# 05-VIDEO_IN_ADC_1.net
KiCad netlist of a schematic drawn in Altium Designer
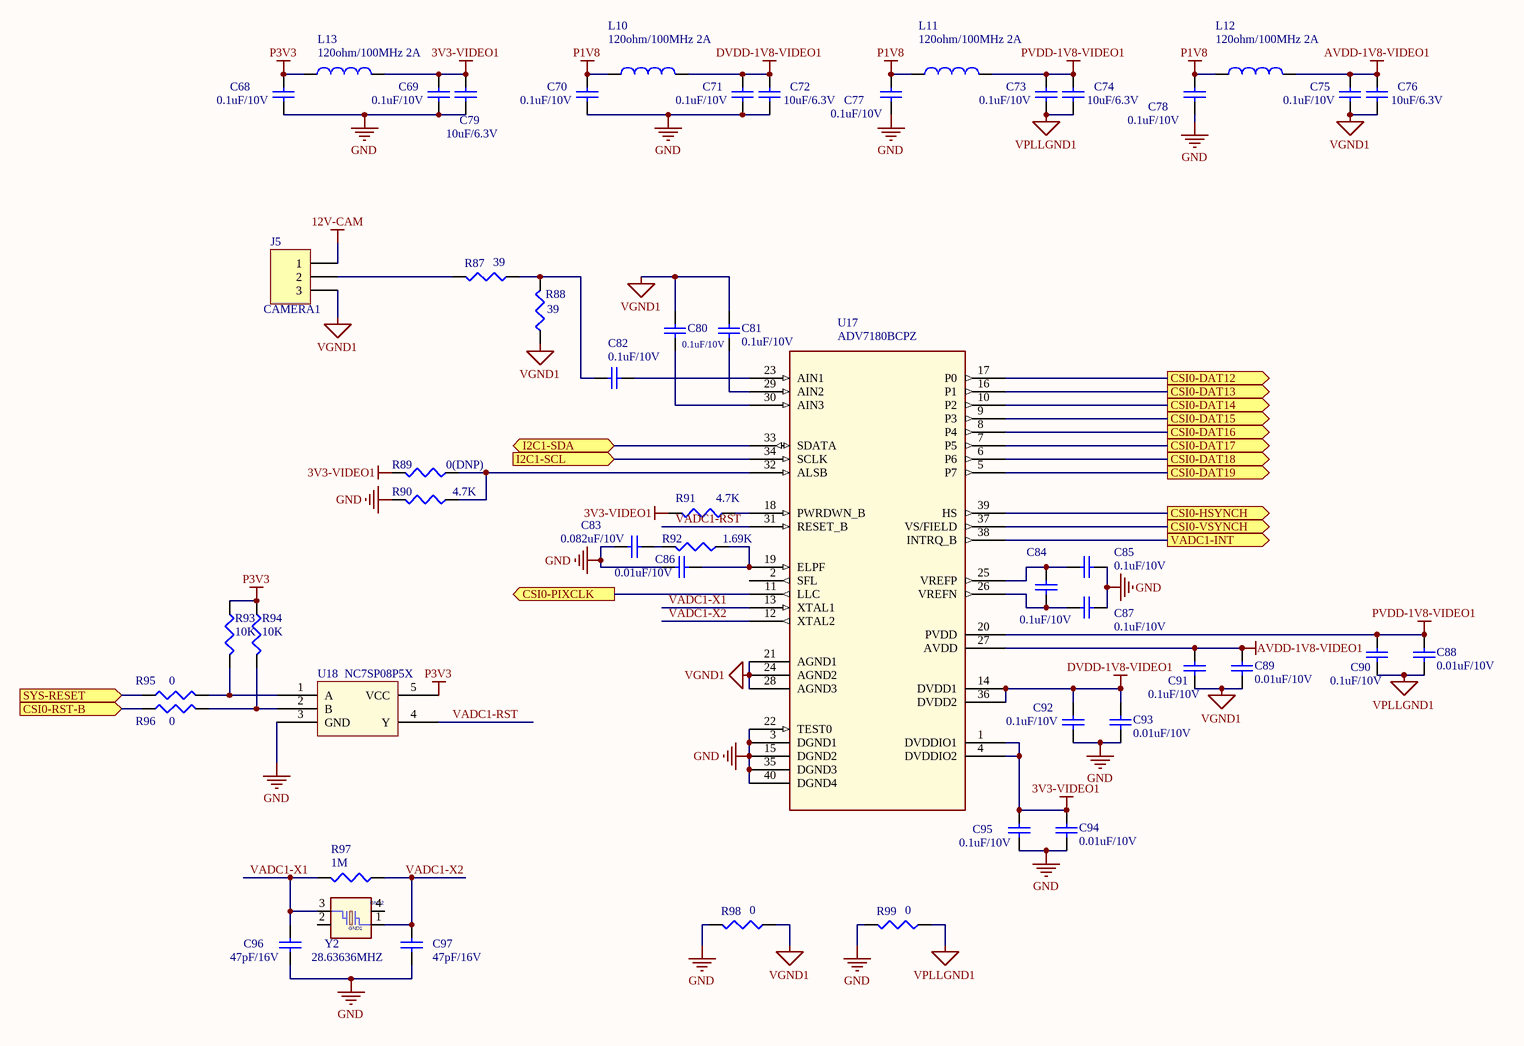
[diagram p0: 05-VIDEO_IN_ADC_1.SchDoc]

(export (version "E")
  (design (tool "Eeschema 10.0.6"))
  (components
    (comp (ref "C68")
      (value "0.1uF/10V")
      (footprint "0402")
      (description "Capacitor")
      (fields (field (name "PUBLISHER") "Altium Limited"))
      (libsource (lib "Miscellaneous Devices") (part "Cap"))
    )
    (comp (ref "C69")
      (value "0.1uF/10V")
      (footprint "0402")
      (description "Capacitor")
      (fields (field (name "PUBLISHER") "Altium Limited"))
      (libsource (lib "Miscellaneous Devices") (part "Cap"))
    )
    (comp (ref "C70")
      (value "0.1uF/10V")
      (footprint "0402")
      (description "Capacitor")
      (fields (field (name "PUBLISHER") "Altium Limited"))
      (libsource (lib "Miscellaneous Devices") (part "Cap"))
    )
    (comp (ref "C71")
      (value "0.1uF/10V")
      (footprint "0402")
      (description "Capacitor")
      (fields (field (name "PUBLISHER") "Altium Limited"))
      (libsource (lib "Miscellaneous Devices") (part "Cap"))
    )
    (comp (ref "C72")
      (value "10uF/6.3V")
      (footprint "0805")
      (description "Capacitor")
      (fields (field (name "PUBLISHER") "Altium Limited"))
      (libsource (lib "Miscellaneous Devices") (part "Cap"))
    )
    (comp (ref "C73")
      (value "0.1uF/10V")
      (footprint "0402")
      (description "Capacitor")
      (fields (field (name "PUBLISHER") "Altium Limited"))
      (libsource (lib "Miscellaneous Devices") (part "Cap"))
    )
    (comp (ref "C74")
      (value "10uF/6.3V")
      (footprint "0805")
      (description "Capacitor")
      (fields (field (name "PUBLISHER") "Altium Limited"))
      (libsource (lib "Miscellaneous Devices") (part "Cap"))
    )
    (comp (ref "C75")
      (value "0.1uF/10V")
      (footprint "0402")
      (description "Capacitor")
      (fields (field (name "PUBLISHER") "Altium Limited"))
      (libsource (lib "Miscellaneous Devices") (part "Cap"))
    )
    (comp (ref "C76")
      (value "10uF/6.3V")
      (footprint "0805")
      (description "Capacitor")
      (fields (field (name "PUBLISHER") "Altium Limited"))
      (libsource (lib "Miscellaneous Devices") (part "Cap"))
    )
    (comp (ref "C77")
      (value "0.1uF/10V")
      (footprint "0402")
      (description "Capacitor")
      (fields (field (name "PUBLISHER") "Altium Limited"))
      (libsource (lib "Miscellaneous Devices") (part "Cap"))
    )
    (comp (ref "C78")
      (value "0.1uF/10V")
      (footprint "0402")
      (description "Capacitor")
      (fields (field (name "PUBLISHER") "Altium Limited"))
      (libsource (lib "Miscellaneous Devices") (part "Cap"))
    )
    (comp (ref "C79")
      (value "10uF/6.3V")
      (footprint "0805")
      (description "Capacitor")
      (fields (field (name "PUBLISHER") "Altium Limited"))
      (libsource (lib "Miscellaneous Devices") (part "Cap"))
    )
    (comp (ref "C80")
      (value "0.1uF/10V")
      (footprint "0402")
      (description "Capacitor")
      (fields (field (name "PUBLISHER") "Altium Limited"))
      (libsource (lib "Miscellaneous Devices") (part "Cap"))
    )
    (comp (ref "C81")
      (value "0.1uF/10V")
      (footprint "0402")
      (description "Capacitor")
      (fields (field (name "PUBLISHER") "Altium Limited"))
      (libsource (lib "Miscellaneous Devices") (part "Cap"))
    )
    (comp (ref "C82")
      (value "0.1uF/10V")
      (footprint "0402")
      (description "Capacitor")
      (fields (field (name "PUBLISHER") "Altium Limited"))
      (libsource (lib "Miscellaneous Devices") (part "Cap"))
    )
    (comp (ref "C83")
      (value "0.082uF/10V")
      (footprint "0402")
      (description "Capacitor")
      (fields (field (name "PUBLISHER") "Altium Limited"))
      (libsource (lib "Miscellaneous Devices") (part "Cap"))
    )
    (comp (ref "C84")
      (value "0.1uF/10V")
      (footprint "0402")
      (description "Capacitor")
      (fields (field (name "PUBLISHER") "Altium Limited"))
      (libsource (lib "Miscellaneous Devices") (part "Cap"))
    )
    (comp (ref "C85")
      (value "0.1uF/10V")
      (footprint "0402")
      (description "Capacitor")
      (fields (field (name "PUBLISHER") "Altium Limited"))
      (libsource (lib "Miscellaneous Devices") (part "Cap"))
    )
    (comp (ref "C86")
      (value "0.01uF/10V")
      (footprint "0402")
      (description "Capacitor")
      (fields (field (name "PUBLISHER") "Altium Limited"))
      (libsource (lib "Miscellaneous Devices") (part "Cap"))
    )
    (comp (ref "C87")
      (value "0.1uF/10V")
      (footprint "0402")
      (description "Capacitor")
      (fields (field (name "PUBLISHER") "Altium Limited"))
      (libsource (lib "Miscellaneous Devices") (part "Cap"))
    )
    (comp (ref "C88")
      (value "0.01uF/10V")
      (footprint "0402")
      (description "Capacitor")
      (fields (field (name "PUBLISHER") "Altium Limited"))
      (libsource (lib "Miscellaneous Devices") (part "Cap"))
    )
    (comp (ref "C89")
      (value "0.01uF/10V")
      (footprint "0402")
      (description "Capacitor")
      (fields (field (name "PUBLISHER") "Altium Limited"))
      (libsource (lib "Miscellaneous Devices") (part "Cap"))
    )
    (comp (ref "C90")
      (value "0.1uF/10V")
      (footprint "0402")
      (description "Capacitor")
      (fields (field (name "PUBLISHER") "Altium Limited"))
      (libsource (lib "Miscellaneous Devices") (part "Cap"))
    )
    (comp (ref "C91")
      (value "0.1uF/10V")
      (footprint "0402")
      (description "Capacitor")
      (fields (field (name "PUBLISHER") "Altium Limited"))
      (libsource (lib "Miscellaneous Devices") (part "Cap"))
    )
    (comp (ref "C92")
      (value "0.1uF/10V")
      (footprint "0402")
      (description "Capacitor")
      (fields (field (name "PUBLISHER") "Altium Limited"))
      (libsource (lib "Miscellaneous Devices") (part "Cap"))
    )
    (comp (ref "C93")
      (value "0.01uF/10V")
      (footprint "0402")
      (description "Capacitor")
      (fields (field (name "PUBLISHER") "Altium Limited"))
      (libsource (lib "Miscellaneous Devices") (part "Cap"))
    )
    (comp (ref "C94")
      (value "0.01uF/10V")
      (footprint "0402")
      (description "Capacitor")
      (fields (field (name "PUBLISHER") "Altium Limited"))
      (libsource (lib "Miscellaneous Devices") (part "Cap"))
    )
    (comp (ref "C95")
      (value "0.1uF/10V")
      (footprint "0402")
      (description "Capacitor")
      (fields (field (name "PUBLISHER") "Altium Limited"))
      (libsource (lib "Miscellaneous Devices") (part "Cap"))
    )
    (comp (ref "C96")
      (value "47pF/16V")
      (footprint "0402")
      (description "Capacitor")
      (fields (field (name "PUBLISHER") "Altium Limited"))
      (libsource (lib "Miscellaneous Devices") (part "Cap"))
    )
    (comp (ref "C97")
      (value "47pF/16V")
      (footprint "0402")
      (description "Capacitor")
      (fields (field (name "PUBLISHER") "Altium Limited"))
      (libsource (lib "Miscellaneous Devices") (part "Cap"))
    )
    (comp (ref "J5")
      (value "CAMERA1")
      (footprint "CONN-3P")
      (description "Header, 3-Pin")
      (fields (field (name "PUBLISHER") "Altium Limited"))
      (libsource (lib "Miscellaneous Connectors") (part "Header 3"))
    )
    (comp (ref "L10")
      (value "120ohm/100MHz 2A")
      (footprint "0603")
      (description "Inductor")
      (fields (field (name "PUBLISHER") "Altium Limited"))
      (libsource (lib "Miscellaneous Devices") (part "Inductor"))
    )
    (comp (ref "L11")
      (value "120ohm/100MHz 2A")
      (footprint "0603")
      (description "Inductor")
      (fields (field (name "PUBLISHER") "Altium Limited"))
      (libsource (lib "Miscellaneous Devices") (part "Inductor"))
    )
    (comp (ref "L12")
      (value "120ohm/100MHz 2A")
      (footprint "0603")
      (description "Inductor")
      (fields (field (name "PUBLISHER") "Altium Limited"))
      (libsource (lib "Miscellaneous Devices") (part "Inductor"))
    )
    (comp (ref "L13")
      (value "120ohm/100MHz 2A")
      (footprint "0603")
      (description "Inductor")
      (fields (field (name "PUBLISHER") "Altium Limited"))
      (libsource (lib "Miscellaneous Devices") (part "Inductor"))
    )
    (comp (ref "R87") (value "39") (footprint "0402") (libsource (lib "*") (part "CR16-1003FM")))
    (comp (ref "R88") (value "39") (footprint "0402") (libsource (lib "*") (part "CR16-1003FM")))
    (comp (ref "R89") (value "0(DNP)") (footprint "0402") (libsource (lib "*") (part "CR16-1003FM")))
    (comp (ref "R90") (value "4.7K") (footprint "0402") (libsource (lib "*") (part "CR16-1003FM")))
    (comp (ref "R91") (value "4.7K") (footprint "0402") (libsource (lib "*") (part "CR16-1003FM")))
    (comp (ref "R92") (value "1.69K") (footprint "0402") (libsource (lib "*") (part "CR16-1003FM")))
    (comp (ref "R93") (value "10K") (footprint "0402") (libsource (lib "*") (part "CR16-1003FM")))
    (comp (ref "R94") (value "10K") (footprint "0402") (libsource (lib "*") (part "CR16-1003FM")))
    (comp (ref "R95") (value "0") (footprint "0402") (libsource (lib "*") (part "CR16-1003FM")))
    (comp (ref "R96") (value "0") (footprint "0402") (libsource (lib "*") (part "CR16-1003FM")))
    (comp (ref "R97") (value "1M") (footprint "0402") (libsource (lib "*") (part "CR16-1003FM")))
    (comp (ref "R98") (value "0") (footprint "0402") (libsource (lib "*") (part "CR16-1003FM")))
    (comp (ref "R99") (value "0") (footprint "0402") (libsource (lib "*") (part "CR16-1003FM")))
    (comp (ref "U17")
      (value "ADV7180BCPZ")
      (footprint "LFCSP40")
      (libsource (lib "Schlib") (part "ADV7180BCPZ"))
    )
    (comp (ref "U18") (value "NC7SP08P5X") (footprint "SC70") (libsource (lib "Schlib") (part "NC7SP08P5X")))
    (comp (ref "Y2")
      (value "28.63636MHZ")
      (footprint "XTAL4_SX_3225")
      (description "XTAL 28.63636MHZ 10PF RSN -- SMT")
      (libsource (lib "*") (part "CRYSTAL_JXS63"))
    )
  )
  (nets
    (net (code "1") (name "/CSI0-DAT12") (class "Default")
      (node (ref "U17") (pin "17") (pinfunction "P0_17") (pintype "output"))
    )
    (net (code "2") (name "/CSI0-DAT13") (class "Default")
      (node (ref "U17") (pin "16") (pinfunction "P1_16") (pintype "output"))
    )
    (net (code "3") (name "/CSI0-DAT14") (class "Default")
      (node (ref "U17") (pin "10") (pinfunction "P2_10") (pintype "output"))
    )
    (net (code "4") (name "/CSI0-DAT15") (class "Default")
      (node (ref "U17") (pin "9") (pinfunction "P3_9") (pintype "output"))
    )
    (net (code "5") (name "/CSI0-DAT16") (class "Default")
      (node (ref "U17") (pin "8") (pinfunction "P4_8") (pintype "output"))
    )
    (net (code "6") (name "/CSI0-DAT17") (class "Default")
      (node (ref "U17") (pin "7") (pinfunction "P5_7") (pintype "output"))
    )
    (net (code "7") (name "/CSI0-DAT18") (class "Default")
      (node (ref "U17") (pin "6") (pinfunction "P6_6") (pintype "output"))
    )
    (net (code "8") (name "/CSI0-DAT19") (class "Default")
      (node (ref "U17") (pin "5") (pinfunction "P7_5") (pintype "output"))
    )
    (net (code "9") (name "/CSI0-HSYNCH") (class "Default")
      (node (ref "U17") (pin "39") (pinfunction "HS_39") (pintype "output"))
    )
    (net (code "10") (name "/CSI0-PIXCLK") (class "Default")
      (node (ref "U17") (pin "11") (pinfunction "LLC_11") (pintype "output"))
    )
    (net (code "11") (name "/CSI0-RST-B") (class "Default")
      (node (ref "R96") (pin "1") (pinfunction "1_1") (pintype "passive"))
    )
    (net (code "12") (name "/CSI0-VSYNCH") (class "Default")
      (node (ref "U17") (pin "37") (pinfunction "VS/FIELD_37") (pintype "output"))
    )
    (net (code "13") (name "/I2C1-SCL") (class "Default")
      (node (ref "U17") (pin "34") (pinfunction "SCLK_34") (pintype "input"))
    )
    (net (code "14") (name "/I2C1-SDA") (class "Default")
      (node (ref "U17") (pin "33") (pinfunction "SDATA_33") (pintype "bidirectional"))
    )
    (net (code "15") (name "/SYS-RESET") (class "Default")
      (node (ref "R95") (pin "1") (pinfunction "1_1") (pintype "passive"))
    )
    (net (code "16") (name "/VADC1-INT") (class "Default")
      (node (ref "U17") (pin "38") (pinfunction "INTRQ_B_38") (pintype "output"))
    )
    (net (code "17") (name "/VADC1-RST") (class "Default")
      (node (ref "U17") (pin "31") (pinfunction "RESET_B_31") (pintype "input"))
      (node (ref "U18") (pin "4") (pinfunction "Y_4") (pintype "passive"))
    )
    (net (code "18") (name "/VADC1-X1") (class "Default")
      (node (ref "C96") (pin "2") (pinfunction "2_2") (pintype "passive"))
      (node (ref "R97") (pin "2") (pinfunction "2_2") (pintype "passive"))
      (node (ref "U17") (pin "13") (pinfunction "XTAL1_13") (pintype "input"))
      (node (ref "Y2") (pin "3") (pinfunction "3_3") (pintype "passive"))
    )
    (net (code "19") (name "/VADC1-X2") (class "Default")
      (node (ref "C97") (pin "2") (pinfunction "2_2") (pintype "passive"))
      (node (ref "R97") (pin "1") (pinfunction "1_1") (pintype "passive"))
      (node (ref "U17") (pin "12") (pinfunction "XTAL2_12") (pintype "output"))
      (node (ref "Y2") (pin "1") (pinfunction "1_1") (pintype "passive"))
    )
    (net (code "20") (name "3V3-VIDEO1") (class "Default")
      (node (ref "C69") (pin "1") (pinfunction "1_1") (pintype "passive"))
      (node (ref "C79") (pin "1") (pinfunction "1_1") (pintype "passive"))
      (node (ref "C94") (pin "2") (pinfunction "2_2") (pintype "passive"))
      (node (ref "C95") (pin "2") (pinfunction "2_2") (pintype "passive"))
      (node (ref "L13") (pin "2") (pinfunction "2_2") (pintype "passive"))
      (node (ref "R89") (pin "2") (pinfunction "2_2") (pintype "passive"))
      (node (ref "R91") (pin "2") (pinfunction "2_2") (pintype "passive"))
      (node (ref "U17") (pin "1") (pinfunction "DVDDIO1_1") (pintype "power_in"))
      (node (ref "U17") (pin "4") (pinfunction "DVDDIO2_4") (pintype "power_in"))
    )
    (net (code "21") (name "12V-CAM") (class "Default")
      (node (ref "J5") (pin "1") (pinfunction "1_1") (pintype "passive"))
    )
    (net (code "22") (name "AVDD-1V8-VIDEO1") (class "Default")
      (node (ref "C75") (pin "1") (pinfunction "1_1") (pintype "passive"))
      (node (ref "C76") (pin "1") (pinfunction "1_1") (pintype "passive"))
      (node (ref "C89") (pin "2") (pinfunction "2_2") (pintype "passive"))
      (node (ref "C91") (pin "2") (pinfunction "2_2") (pintype "passive"))
      (node (ref "L12") (pin "2") (pinfunction "2_2") (pintype "passive"))
      (node (ref "U17") (pin "27") (pinfunction "AVDD_27") (pintype "power_in"))
    )
    (net (code "23") (name "DVDD-1V8-VIDEO1") (class "Default")
      (node (ref "C71") (pin "1") (pinfunction "1_1") (pintype "passive"))
      (node (ref "C72") (pin "1") (pinfunction "1_1") (pintype "passive"))
      (node (ref "C92") (pin "2") (pinfunction "2_2") (pintype "passive"))
      (node (ref "C93") (pin "2") (pinfunction "2_2") (pintype "passive"))
      (node (ref "L10") (pin "2") (pinfunction "2_2") (pintype "passive"))
      (node (ref "U17") (pin "14") (pinfunction "DVDD1_14") (pintype "power_in"))
      (node (ref "U17") (pin "36") (pinfunction "DVDD2_36") (pintype "power_in"))
    )
    (net (code "24") (name "GND") (class "Default")
      (node (ref "C68") (pin "2") (pinfunction "2_2") (pintype "passive"))
      (node (ref "C69") (pin "2") (pinfunction "2_2") (pintype "passive"))
      (node (ref "C70") (pin "2") (pinfunction "2_2") (pintype "passive"))
      (node (ref "C71") (pin "2") (pinfunction "2_2") (pintype "passive"))
      (node (ref "C72") (pin "2") (pinfunction "2_2") (pintype "passive"))
      (node (ref "C77") (pin "2") (pinfunction "2_2") (pintype "passive"))
      (node (ref "C78") (pin "2") (pinfunction "2_2") (pintype "passive"))
      (node (ref "C79") (pin "2") (pinfunction "2_2") (pintype "passive"))
      (node (ref "C83") (pin "1") (pinfunction "1_1") (pintype "passive"))
      (node (ref "C85") (pin "1") (pinfunction "1_1") (pintype "passive"))
      (node (ref "C86") (pin "1") (pinfunction "1_1") (pintype "passive"))
      (node (ref "C87") (pin "2") (pinfunction "2_2") (pintype "passive"))
      (node (ref "C92") (pin "1") (pinfunction "1_1") (pintype "passive"))
      (node (ref "C93") (pin "1") (pinfunction "1_1") (pintype "passive"))
      (node (ref "C94") (pin "1") (pinfunction "1_1") (pintype "passive"))
      (node (ref "C95") (pin "1") (pinfunction "1_1") (pintype "passive"))
      (node (ref "C96") (pin "1") (pinfunction "1_1") (pintype "passive"))
      (node (ref "C97") (pin "1") (pinfunction "1_1") (pintype "passive"))
      (node (ref "R90") (pin "2") (pinfunction "2_2") (pintype "passive"))
      (node (ref "R98") (pin "2") (pinfunction "2_2") (pintype "passive"))
      (node (ref "R99") (pin "2") (pinfunction "2_2") (pintype "passive"))
      (node (ref "U17") (pin "15") (pinfunction "DGND2_15") (pintype "power_in"))
      (node (ref "U17") (pin "22") (pinfunction "TEST0_22") (pintype "input"))
      (node (ref "U17") (pin "3") (pinfunction "DGND1_3") (pintype "power_in"))
      (node (ref "U17") (pin "35") (pinfunction "DGND3_35") (pintype "power_in"))
      (node (ref "U17") (pin "40") (pinfunction "DGND4_40") (pintype "power_in"))
      (node (ref "U18") (pin "3") (pinfunction "GND_3") (pintype "passive"))
    )
    (net (code "25") (name "Net-(C82-Pad1)") (class "Default")
      (node (ref "C82") (pin "1") (pinfunction "1_1") (pintype "passive"))
      (node (ref "R87") (pin "1") (pinfunction "1_1") (pintype "passive"))
      (node (ref "R88") (pin "2") (pinfunction "2_2") (pintype "passive"))
    )
    (net (code "26") (name "Net-(C83-Pad2)") (class "Default")
      (node (ref "C83") (pin "2") (pinfunction "2_2") (pintype "passive"))
      (node (ref "R92") (pin "2") (pinfunction "2_2") (pintype "passive"))
    )
    (net (code "27") (name "Net-(J5-Pad2)") (class "Default")
      (node (ref "J5") (pin "2") (pinfunction "2_2") (pintype "passive"))
      (node (ref "R87") (pin "2") (pinfunction "2_2") (pintype "passive"))
    )
    (net (code "28") (name "Net-(U17-AIN1)") (class "Default")
      (node (ref "C82") (pin "2") (pinfunction "2_2") (pintype "passive"))
      (node (ref "U17") (pin "23") (pinfunction "AIN1_23") (pintype "input"))
    )
    (net (code "29") (name "Net-(U17-AIN2)") (class "Default")
      (node (ref "C81") (pin "1") (pinfunction "1_1") (pintype "passive"))
      (node (ref "U17") (pin "29") (pinfunction "AIN2_29") (pintype "input"))
    )
    (net (code "30") (name "Net-(U17-AIN3)") (class "Default")
      (node (ref "C80") (pin "1") (pinfunction "1_1") (pintype "passive"))
      (node (ref "U17") (pin "30") (pinfunction "AIN3_30") (pintype "input"))
    )
    (net (code "31") (name "Net-(U17-ALSB)") (class "Default")
      (node (ref "R89") (pin "1") (pinfunction "1_1") (pintype "passive"))
      (node (ref "R90") (pin "1") (pinfunction "1_1") (pintype "passive"))
      (node (ref "U17") (pin "32") (pinfunction "ALSB_32") (pintype "input"))
    )
    (net (code "32") (name "Net-(U17-ELPF)") (class "Default")
      (node (ref "C86") (pin "2") (pinfunction "2_2") (pintype "passive"))
      (node (ref "R92") (pin "1") (pinfunction "1_1") (pintype "passive"))
      (node (ref "U17") (pin "19") (pinfunction "ELPF_19") (pintype "input"))
    )
    (net (code "33") (name "Net-(U17-PWRDWN_B)") (class "Default")
      (node (ref "R91") (pin "1") (pinfunction "1_1") (pintype "passive"))
      (node (ref "U17") (pin "18") (pinfunction "PWRDWN_B_18") (pintype "input"))
    )
    (net (code "34") (name "Net-(U17-VREFN)") (class "Default")
      (node (ref "C84") (pin "1") (pinfunction "1_1") (pintype "passive"))
      (node (ref "C87") (pin "1") (pinfunction "1_1") (pintype "passive"))
      (node (ref "U17") (pin "26") (pinfunction "VREFN_26") (pintype "output"))
    )
    (net (code "35") (name "Net-(U17-VREFP)") (class "Default")
      (node (ref "C84") (pin "2") (pinfunction "2_2") (pintype "passive"))
      (node (ref "C85") (pin "2") (pinfunction "2_2") (pintype "passive"))
      (node (ref "U17") (pin "25") (pinfunction "VREFP_25") (pintype "output"))
    )
    (net (code "36") (name "Net-(U18-A)") (class "Default")
      (node (ref "R93") (pin "2") (pinfunction "2_2") (pintype "passive"))
      (node (ref "R95") (pin "2") (pinfunction "2_2") (pintype "passive"))
      (node (ref "U18") (pin "1") (pinfunction "A_1") (pintype "passive"))
    )
    (net (code "37") (name "Net-(U18-B)") (class "Default")
      (node (ref "R94") (pin "2") (pinfunction "2_2") (pintype "passive"))
      (node (ref "R96") (pin "2") (pinfunction "2_2") (pintype "passive"))
      (node (ref "U18") (pin "2") (pinfunction "B_2") (pintype "passive"))
    )
    (net (code "38") (name "P1V8") (class "Default")
      (node (ref "C70") (pin "1") (pinfunction "1_1") (pintype "passive"))
      (node (ref "C77") (pin "1") (pinfunction "1_1") (pintype "passive"))
      (node (ref "C78") (pin "1") (pinfunction "1_1") (pintype "passive"))
      (node (ref "L10") (pin "1") (pinfunction "1_1") (pintype "passive"))
      (node (ref "L11") (pin "1") (pinfunction "1_1") (pintype "passive"))
      (node (ref "L12") (pin "1") (pinfunction "1_1") (pintype "passive"))
    )
    (net (code "39") (name "P3V3") (class "Default")
      (node (ref "C68") (pin "1") (pinfunction "1_1") (pintype "passive"))
      (node (ref "L13") (pin "1") (pinfunction "1_1") (pintype "passive"))
      (node (ref "R93") (pin "1") (pinfunction "1_1") (pintype "passive"))
      (node (ref "R94") (pin "1") (pinfunction "1_1") (pintype "passive"))
      (node (ref "U18") (pin "5") (pinfunction "VCC_5") (pintype "passive"))
    )
    (net (code "40") (name "PVDD-1V8-VIDEO1") (class "Default")
      (node (ref "C73") (pin "1") (pinfunction "1_1") (pintype "passive"))
      (node (ref "C74") (pin "1") (pinfunction "1_1") (pintype "passive"))
      (node (ref "C88") (pin "2") (pinfunction "2_2") (pintype "passive"))
      (node (ref "C90") (pin "2") (pinfunction "2_2") (pintype "passive"))
      (node (ref "L11") (pin "2") (pinfunction "2_2") (pintype "passive"))
      (node (ref "U17") (pin "20") (pinfunction "PVDD_20") (pintype "power_in"))
    )
    (net (code "41") (name "VGND1") (class "Default")
      (node (ref "C75") (pin "2") (pinfunction "2_2") (pintype "passive"))
      (node (ref "C76") (pin "2") (pinfunction "2_2") (pintype "passive"))
      (node (ref "C80") (pin "2") (pinfunction "2_2") (pintype "passive"))
      (node (ref "C81") (pin "2") (pinfunction "2_2") (pintype "passive"))
      (node (ref "C89") (pin "1") (pinfunction "1_1") (pintype "passive"))
      (node (ref "C91") (pin "1") (pinfunction "1_1") (pintype "passive"))
      (node (ref "J5") (pin "3") (pinfunction "3_3") (pintype "passive"))
      (node (ref "R88") (pin "1") (pinfunction "1_1") (pintype "passive"))
      (node (ref "R98") (pin "1") (pinfunction "1_1") (pintype "passive"))
      (node (ref "U17") (pin "21") (pinfunction "AGND1_21") (pintype "power_in"))
      (node (ref "U17") (pin "24") (pinfunction "AGND2_24") (pintype "power_in"))
      (node (ref "U17") (pin "28") (pinfunction "AGND3_28") (pintype "power_in"))
    )
    (net (code "42") (name "VPLLGND1") (class "Default")
      (node (ref "C73") (pin "2") (pinfunction "2_2") (pintype "passive"))
      (node (ref "C74") (pin "2") (pinfunction "2_2") (pintype "passive"))
      (node (ref "C88") (pin "1") (pinfunction "1_1") (pintype "passive"))
      (node (ref "C90") (pin "1") (pinfunction "1_1") (pintype "passive"))
      (node (ref "R99") (pin "1") (pinfunction "1_1") (pintype "passive"))
    )
    (net (code "43") (name "unconnected-(U17-SFL-Pad2)") (class "Default")
      (node (ref "U17") (pin "2") (pinfunction "SFL_2") (pintype "output"))
    )
    (net (code "44") (name "unconnected-(Y2-GND1-Pad2)") (class "Default")
      (node (ref "Y2") (pin "2") (pinfunction "GND1_2") (pintype "power_in"))
    )
    (net (code "45") (name "unconnected-(Y2-GND2-Pad4)") (class "Default")
      (node (ref "Y2") (pin "4") (pinfunction "GND2_4") (pintype "power_in"))
    )
  )
)
